# io.net
KiCad netlist of a schematic drawn in Altium Designer
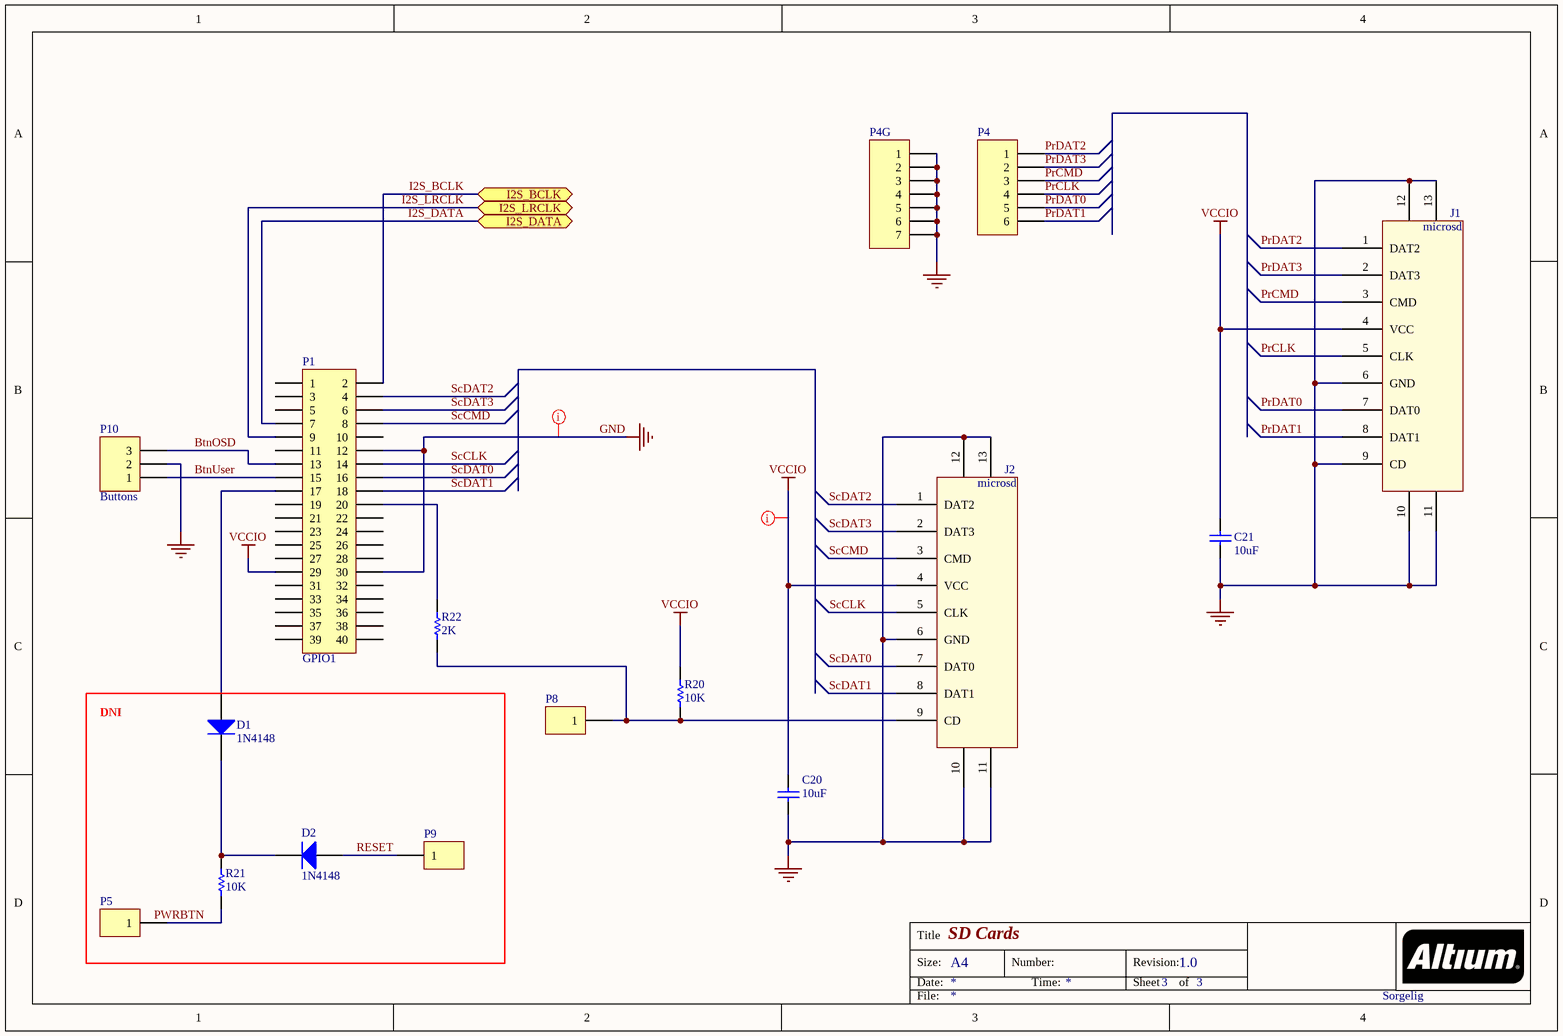
[diagram p0: io.SchDoc]

(export (version "E")
  (design (tool "Eeschema 10.0.6"))
  (components
    (comp (ref "C20")
      (value "10uF")
      (footprint "C0805")
      (description "Ceramic Chip Capacitor - Standard")
      (fields (field (name "Comment") "C0805") (field (name "PUBLISHER") "Altium Limited"))
      (libsource (lib "lib") (part "C0805"))
    )
    (comp (ref "C21")
      (value "10uF")
      (footprint "C0805")
      (description "Ceramic Chip Capacitor - Standard")
      (fields (field (name "Comment") "C0805") (field (name "PUBLISHER") "Altium Limited"))
      (libsource (lib "lib") (part "C0805"))
    )
    (comp (ref "D1")
      (value "1N4148")
      (footprint "DIODE")
      (description "Default Diode")
      (fields (field (name "PUBLISHER") "Altium Limited"))
      (libsource (lib "Miscellaneous Devices") (part "Diode"))
    )
    (comp (ref "D2")
      (value "1N4148")
      (footprint "DIODE")
      (description "Default Diode")
      (fields (field (name "PUBLISHER") "Altium Limited"))
      (libsource (lib "Miscellaneous Devices") (part "Diode"))
    )
    (comp (ref "J1") (value "microsd") (footprint "microsd") (libsource (lib "lib") (part "microsd")))
    (comp (ref "J2") (value "microsd") (footprint "microsd") (libsource (lib "lib") (part "microsd")))
    (comp (ref "P1")
      (value "GPIO1")
      (footprint "HDR20x2")
      (description "Header, 20-Pin, Dual row")
      (fields (field (name "PUBLISHER") "Altium Limited"))
      (libsource (lib "Miscellaneous Connectors") (part "Header 20X2"))
    )
    (comp (ref "P4")
      (value "Header 6")
      (footprint "HDR1X6")
      (description "Header, 6-Pin")
      (fields (field (name "PUBLISHER") "Altium Limited"))
      (libsource (lib "Miscellaneous Connectors") (part "Header 6"))
    )
    (comp (ref "P4G")
      (value "Header 7")
      (footprint "HDR1X7")
      (description "Header, 7-Pin")
      (fields (field (name "PUBLISHER") "Altium Limited"))
      (libsource (lib "Miscellaneous Connectors") (part "Header 7"))
    )
    (comp (ref "P5") (value "Header 1") (footprint "Header 1") (libsource (lib "lib") (part "Header 1")))
    (comp (ref "P8") (value "Header 1") (footprint "Header 1") (libsource (lib "lib") (part "Header 1")))
    (comp (ref "P9") (value "Header 1") (footprint "Header 1") (libsource (lib "") (part "Header 1_1")))
    (comp (ref "P10")
      (value "Buttons")
      (footprint "HDR1X3")
      (description "Header, 3-Pin")
      (fields (field (name "PUBLISHER") "Altium Limited"))
      (libsource (lib "Miscellaneous Connectors") (part "Header 3"))
    )
    (comp (ref "R20")
      (value "10K")
      (footprint "R0805")
      (fields (field (name "PUBLISHER") "Altium Limited"))
      (libsource (lib "lib") (part "R0805"))
    )
    (comp (ref "R21")
      (value "10K")
      (footprint "R0805")
      (fields (field (name "PUBLISHER") "Altium Limited"))
      (libsource (lib "lib") (part "R0805"))
    )
    (comp (ref "R22")
      (value "2K")
      (footprint "R0805")
      (fields (field (name "PUBLISHER") "Altium Limited"))
      (libsource (lib "lib") (part "R0805"))
    )
  )
  (nets
    (net (code "1") (name "/BtnOSD") (class "Default")
      (node (ref "P1") (pin "13") (pinfunction "13_13") (pintype "passive"))
      (node (ref "P10") (pin "3") (pinfunction "3_3") (pintype "passive"))
    )
    (net (code "2") (name "/BtnUser") (class "Default")
      (node (ref "P1") (pin "15") (pinfunction "15_15") (pintype "passive"))
      (node (ref "P10") (pin "1") (pinfunction "1_1") (pintype "passive"))
    )
    (net (code "3") (name "/I2S_BCLK") (class "Default")
      (node (ref "P1") (pin "2") (pinfunction "2_2") (pintype "passive"))
    )
    (net (code "4") (name "/I2S_DATA") (class "Default")
      (node (ref "P1") (pin "7") (pinfunction "7_7") (pintype "passive"))
    )
    (net (code "5") (name "/I2S_LRCLK") (class "Default")
      (node (ref "P1") (pin "9") (pinfunction "9_9") (pintype "passive"))
    )
    (net (code "7") (name "/PrCLK") (class "Default")
      (node (ref "J1") (pin "5") (pinfunction "CLK_5") (pintype "passive"))
      (node (ref "P4") (pin "4") (pinfunction "4_4") (pintype "passive"))
    )
    (net (code "8") (name "/PrCMD") (class "Default")
      (node (ref "J1") (pin "3") (pinfunction "CMD_3") (pintype "passive"))
      (node (ref "P4") (pin "3") (pinfunction "3_3") (pintype "passive"))
    )
    (net (code "9") (name "/PrDAT0") (class "Default")
      (node (ref "J1") (pin "7") (pinfunction "DAT0_7") (pintype "passive"))
      (node (ref "P4") (pin "5") (pinfunction "5_5") (pintype "passive"))
    )
    (net (code "10") (name "/PrDAT1") (class "Default")
      (node (ref "J1") (pin "8") (pinfunction "DAT1_8") (pintype "passive"))
      (node (ref "P4") (pin "6") (pinfunction "6_6") (pintype "passive"))
    )
    (net (code "11") (name "/PrDAT2") (class "Default")
      (node (ref "J1") (pin "1") (pinfunction "DAT2_1") (pintype "passive"))
      (node (ref "P4") (pin "1") (pinfunction "1_1") (pintype "passive"))
    )
    (net (code "12") (name "/PrDAT3") (class "Default")
      (node (ref "J1") (pin "2") (pinfunction "DAT3_2") (pintype "passive"))
      (node (ref "P4") (pin "2") (pinfunction "2_2") (pintype "passive"))
    )
    (net (code "13") (name "/RESET") (class "Default")
      (node (ref "D2") (pin "1") (pinfunction "A_1") (pintype "passive"))
      (node (ref "P9") (pin "1") (pinfunction "1_1") (pintype "passive"))
    )
    (net (code "14") (name "/ScCLK") (class "Default")
      (node (ref "J2") (pin "5") (pinfunction "CLK_5") (pintype "passive"))
      (node (ref "P1") (pin "14") (pinfunction "14_14") (pintype "passive"))
    )
    (net (code "15") (name "/ScCMD") (class "Default")
      (node (ref "J2") (pin "3") (pinfunction "CMD_3") (pintype "passive"))
      (node (ref "P1") (pin "8") (pinfunction "8_8") (pintype "passive"))
    )
    (net (code "16") (name "/ScDAT0") (class "Default")
      (node (ref "J2") (pin "7") (pinfunction "DAT0_7") (pintype "passive"))
      (node (ref "P1") (pin "16") (pinfunction "16_16") (pintype "passive"))
    )
    (net (code "17") (name "/ScDAT1") (class "Default")
      (node (ref "J2") (pin "8") (pinfunction "DAT1_8") (pintype "passive"))
      (node (ref "P1") (pin "18") (pinfunction "18_18") (pintype "passive"))
    )
    (net (code "18") (name "/ScDAT2") (class "Default")
      (node (ref "J2") (pin "1") (pinfunction "DAT2_1") (pintype "passive"))
      (node (ref "P1") (pin "4") (pinfunction "4_4") (pintype "passive"))
    )
    (net (code "19") (name "/ScDAT3") (class "Default")
      (node (ref "J2") (pin "2") (pinfunction "DAT3_2") (pintype "passive"))
      (node (ref "P1") (pin "6") (pinfunction "6_6") (pintype "passive"))
    )
    (net (code "20") (name "GND") (class "Default")
      (node (ref "C20") (pin "1") (pinfunction "1_1") (pintype "passive"))
      (node (ref "C21") (pin "1") (pinfunction "1_1") (pintype "passive"))
      (node (ref "J1") (pin "10") (pinfunction "GND_10") (pintype "passive"))
      (node (ref "J1") (pin "11") (pinfunction "GND_11") (pintype "passive"))
      (node (ref "J1") (pin "12") (pinfunction "GND_12") (pintype "passive"))
      (node (ref "J1") (pin "13") (pinfunction "GND_13") (pintype "passive"))
      (node (ref "J1") (pin "6") (pinfunction "GND_6") (pintype "passive"))
      (node (ref "J1") (pin "9") (pinfunction "CD_9") (pintype "passive"))
      (node (ref "J2") (pin "10") (pinfunction "GND_10") (pintype "passive"))
      (node (ref "J2") (pin "11") (pinfunction "GND_11") (pintype "passive"))
      (node (ref "J2") (pin "12") (pinfunction "GND_12") (pintype "passive"))
      (node (ref "J2") (pin "13") (pinfunction "GND_13") (pintype "passive"))
      (node (ref "J2") (pin "6") (pinfunction "GND_6") (pintype "passive"))
      (node (ref "P1") (pin "12") (pinfunction "12_12") (pintype "passive"))
      (node (ref "P1") (pin "30") (pinfunction "30_30") (pintype "passive"))
      (node (ref "P10") (pin "2") (pinfunction "2_2") (pintype "passive"))
      (node (ref "P4G") (pin "1") (pinfunction "1_1") (pintype "passive"))
      (node (ref "P4G") (pin "2") (pinfunction "2_2") (pintype "passive"))
      (node (ref "P4G") (pin "3") (pinfunction "3_3") (pintype "passive"))
      (node (ref "P4G") (pin "4") (pinfunction "4_4") (pintype "passive"))
      (node (ref "P4G") (pin "5") (pinfunction "5_5") (pintype "passive"))
      (node (ref "P4G") (pin "6") (pinfunction "6_6") (pintype "passive"))
      (node (ref "P4G") (pin "7") (pinfunction "7_7") (pintype "passive"))
    )
    (net (code "21") (name "Net-(D1-A)") (class "Default")
      (node (ref "D1") (pin "1") (pinfunction "A_1") (pintype "passive"))
      (node (ref "P1") (pin "17") (pinfunction "17_17") (pintype "passive"))
    )
    (net (code "22") (name "Net-(D1-K)") (class "Default")
      (node (ref "D1") (pin "2") (pinfunction "K_2") (pintype "passive"))
      (node (ref "D2") (pin "2") (pinfunction "K_2") (pintype "passive"))
      (node (ref "R21") (pin "1") (pinfunction "1_1") (pintype "passive"))
    )
    (net (code "23") (name "Net-(J2-CD)") (class "Default")
      (node (ref "J2") (pin "9") (pinfunction "CD_9") (pintype "passive"))
      (node (ref "P8") (pin "1") (pinfunction "1_1") (pintype "passive"))
      (node (ref "R20") (pin "1") (pinfunction "1_1") (pintype "passive"))
      (node (ref "R22") (pin "1") (pinfunction "1_1") (pintype "passive"))
    )
    (net (code "24") (name "Net-(P1-Pad20)") (class "Default")
      (node (ref "P1") (pin "20") (pinfunction "20_20") (pintype "passive"))
      (node (ref "R22") (pin "2") (pinfunction "2_2") (pintype "passive"))
    )
    (net (code "25") (name "Net-(P5-Pad1)") (class "Default")
      (node (ref "P5") (pin "1") (pinfunction "1_1") (pintype "passive"))
      (node (ref "R21") (pin "2") (pinfunction "2_2") (pintype "passive"))
    )
    (net (code "26") (name "VCCIO") (class "Default")
      (node (ref "C20") (pin "2") (pinfunction "2_2") (pintype "passive"))
      (node (ref "C21") (pin "2") (pinfunction "2_2") (pintype "passive"))
      (node (ref "J1") (pin "4") (pinfunction "VCC_4") (pintype "power_in"))
      (node (ref "J2") (pin "4") (pinfunction "VCC_4") (pintype "power_in"))
      (node (ref "P1") (pin "29") (pinfunction "29_29") (pintype "passive"))
      (node (ref "R20") (pin "2") (pinfunction "2_2") (pintype "passive"))
    )
    (net (code "27") (name "unconnected-(P1-Pad1)") (class "Default")
      (node (ref "P1") (pin "1") (pinfunction "1_1") (pintype "passive"))
    )
    (net (code "28") (name "unconnected-(P1-Pad3)") (class "Default")
      (node (ref "P1") (pin "3") (pinfunction "3_3") (pintype "passive"))
    )
    (net (code "29") (name "unconnected-(P1-Pad5)") (class "Default")
      (node (ref "P1") (pin "5") (pinfunction "5_5") (pintype "passive"))
    )
    (net (code "30") (name "unconnected-(P1-Pad10)") (class "Default")
      (node (ref "P1") (pin "10") (pinfunction "10_10") (pintype "passive"))
    )
    (net (code "31") (name "unconnected-(P1-Pad11)") (class "Default")
      (node (ref "P1") (pin "11") (pinfunction "11_11") (pintype "passive"))
    )
    (net (code "32") (name "unconnected-(P1-Pad19)") (class "Default")
      (node (ref "P1") (pin "19") (pinfunction "19_19") (pintype "passive"))
    )
    (net (code "33") (name "unconnected-(P1-Pad21)") (class "Default")
      (node (ref "P1") (pin "21") (pinfunction "21_21") (pintype "passive"))
    )
    (net (code "34") (name "unconnected-(P1-Pad22)") (class "Default")
      (node (ref "P1") (pin "22") (pinfunction "22_22") (pintype "passive"))
    )
    (net (code "35") (name "unconnected-(P1-Pad23)") (class "Default")
      (node (ref "P1") (pin "23") (pinfunction "23_23") (pintype "passive"))
    )
    (net (code "36") (name "unconnected-(P1-Pad24)") (class "Default")
      (node (ref "P1") (pin "24") (pinfunction "24_24") (pintype "passive"))
    )
    (net (code "37") (name "unconnected-(P1-Pad25)") (class "Default")
      (node (ref "P1") (pin "25") (pinfunction "25_25") (pintype "passive"))
    )
    (net (code "38") (name "unconnected-(P1-Pad26)") (class "Default")
      (node (ref "P1") (pin "26") (pinfunction "26_26") (pintype "passive"))
    )
    (net (code "39") (name "unconnected-(P1-Pad27)") (class "Default")
      (node (ref "P1") (pin "27") (pinfunction "27_27") (pintype "passive"))
    )
    (net (code "40") (name "unconnected-(P1-Pad28)") (class "Default")
      (node (ref "P1") (pin "28") (pinfunction "28_28") (pintype "passive"))
    )
    (net (code "41") (name "unconnected-(P1-Pad31)") (class "Default")
      (node (ref "P1") (pin "31") (pinfunction "31_31") (pintype "passive"))
    )
    (net (code "42") (name "unconnected-(P1-Pad32)") (class "Default")
      (node (ref "P1") (pin "32") (pinfunction "32_32") (pintype "passive"))
    )
    (net (code "43") (name "unconnected-(P1-Pad33)") (class "Default")
      (node (ref "P1") (pin "33") (pinfunction "33_33") (pintype "passive"))
    )
    (net (code "44") (name "unconnected-(P1-Pad34)") (class "Default")
      (node (ref "P1") (pin "34") (pinfunction "34_34") (pintype "passive"))
    )
    (net (code "45") (name "unconnected-(P1-Pad35)") (class "Default")
      (node (ref "P1") (pin "35") (pinfunction "35_35") (pintype "passive"))
    )
    (net (code "46") (name "unconnected-(P1-Pad36)") (class "Default")
      (node (ref "P1") (pin "36") (pinfunction "36_36") (pintype "passive"))
    )
    (net (code "47") (name "unconnected-(P1-Pad37)") (class "Default")
      (node (ref "P1") (pin "37") (pinfunction "37_37") (pintype "passive"))
    )
    (net (code "48") (name "unconnected-(P1-Pad38)") (class "Default")
      (node (ref "P1") (pin "38") (pinfunction "38_38") (pintype "passive"))
    )
    (net (code "49") (name "unconnected-(P1-Pad39)") (class "Default")
      (node (ref "P1") (pin "39") (pinfunction "39_39") (pintype "passive"))
    )
    (net (code "50") (name "unconnected-(P1-Pad40)") (class "Default")
      (node (ref "P1") (pin "40") (pinfunction "40_40") (pintype "passive"))
    )
  )
)
